# Sensor_tile.net
KiCad netlist of a schematic drawn in EAGLE
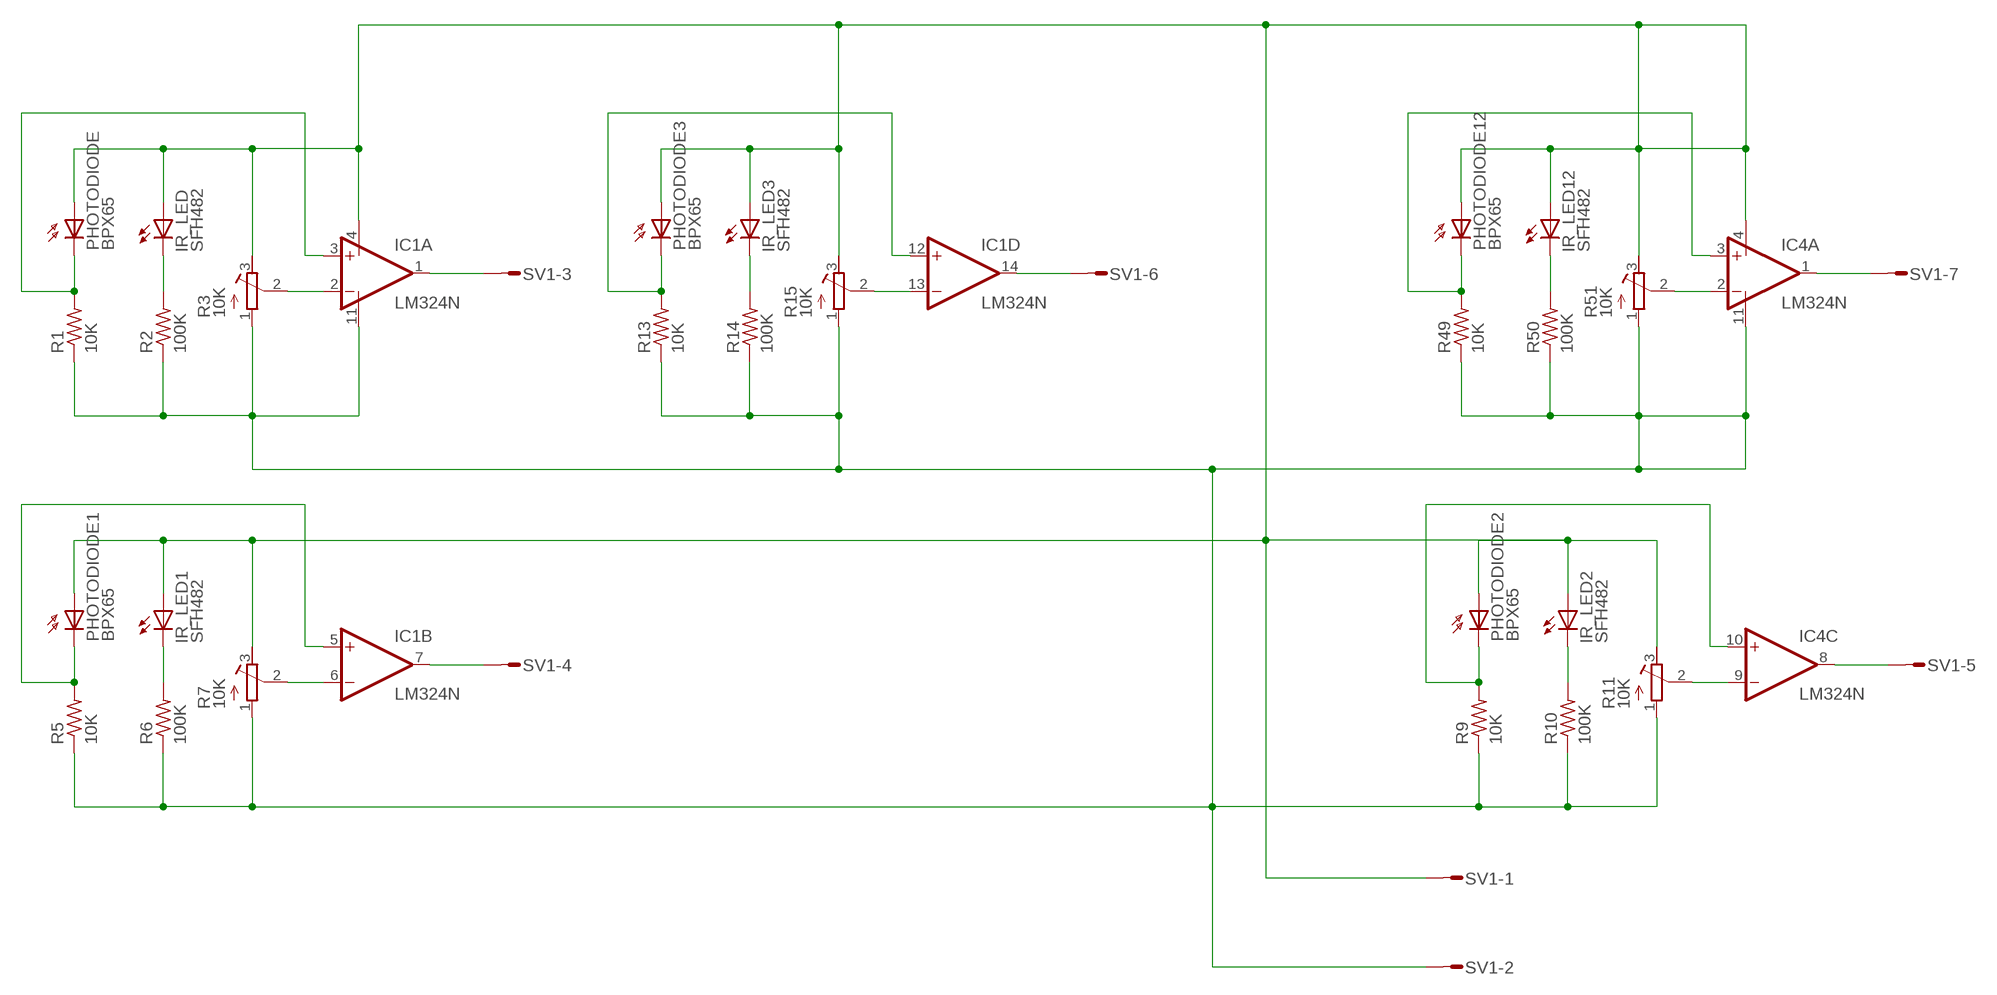
[diagram p0: schematic, sheet 1]

(export (version "E")
  (design (tool "Eeschema 10.0.6"))
  (components
    (comp (ref "IC1")
      (value "LM324N")
      (footprint "eagle-import:DIL14")
      (libsource (lib "eagle-import") (part "LM324N"))
    )
    (comp (ref "IC4")
      (value "LM324N")
      (footprint "eagle-import:DIL14")
      (libsource (lib "eagle-import") (part "LM324N"))
    )
    (comp (ref "IR_LED")
      (value "SFH482")
      (footprint "eagle-import:SFH482")
      (libsource (lib "eagle-import") (part "SFH482"))
    )
    (comp (ref "IR_LED1")
      (value "SFH482")
      (footprint "eagle-import:SFH482")
      (libsource (lib "eagle-import") (part "SFH482"))
    )
    (comp (ref "IR_LED2")
      (value "SFH482")
      (footprint "eagle-import:SFH482")
      (libsource (lib "eagle-import") (part "SFH482"))
    )
    (comp (ref "IR_LED3")
      (value "SFH482")
      (footprint "eagle-import:SFH482")
      (libsource (lib "eagle-import") (part "SFH482"))
    )
    (comp (ref "IR_LED12")
      (value "SFH482")
      (footprint "eagle-import:SFH482")
      (libsource (lib "eagle-import") (part "SFH482"))
    )
    (comp (ref "PHOTODIODE")
      (value "BPX65")
      (footprint "eagle-import:BPX65")
      (fields (field (name "MPN") "BPX65."))
      (libsource (lib "eagle-import") (part "BPX65"))
    )
    (comp (ref "PHOTODIODE1")
      (value "BPX65")
      (footprint "eagle-import:BPX65")
      (fields (field (name "MPN") "BPX65."))
      (libsource (lib "eagle-import") (part "BPX65"))
    )
    (comp (ref "PHOTODIODE2")
      (value "BPX65")
      (footprint "eagle-import:BPX65")
      (fields (field (name "MPN") "BPX65."))
      (libsource (lib "eagle-import") (part "BPX65"))
    )
    (comp (ref "PHOTODIODE3")
      (value "BPX65")
      (footprint "eagle-import:BPX65")
      (fields (field (name "MPN") "BPX65."))
      (libsource (lib "eagle-import") (part "BPX65"))
    )
    (comp (ref "PHOTODIODE12")
      (value "BPX65")
      (footprint "eagle-import:BPX65")
      (fields (field (name "MPN") "BPX65."))
      (libsource (lib "eagle-import") (part "BPX65"))
    )
    (comp (ref "R1")
      (value "10K")
      (footprint "eagle-import:0204_7")
      (libsource (lib "eagle-import") (part "R-US_0204/7"))
    )
    (comp (ref "R2")
      (value "100K")
      (footprint "eagle-import:0204_7")
      (libsource (lib "eagle-import") (part "R-US_0204/7"))
    )
    (comp (ref "R3")
      (value "10K")
      (footprint "eagle-import:RTRIM4G_J")
      (libsource (lib "eagle-import") (part "R-TRIMM4G/J"))
    )
    (comp (ref "R5")
      (value "10K")
      (footprint "eagle-import:0204_7")
      (libsource (lib "eagle-import") (part "R-US_0204/7"))
    )
    (comp (ref "R6")
      (value "100K")
      (footprint "eagle-import:0204_7")
      (libsource (lib "eagle-import") (part "R-US_0204/7"))
    )
    (comp (ref "R7")
      (value "10K")
      (footprint "eagle-import:RTRIM4G_J")
      (libsource (lib "eagle-import") (part "R-TRIMM4G/J"))
    )
    (comp (ref "R9")
      (value "10K")
      (footprint "eagle-import:0204_7")
      (libsource (lib "eagle-import") (part "R-US_0204/7"))
    )
    (comp (ref "R10")
      (value "100K")
      (footprint "eagle-import:0204_7")
      (libsource (lib "eagle-import") (part "R-US_0204/7"))
    )
    (comp (ref "R11")
      (value "10K")
      (footprint "eagle-import:RTRIM4G_J")
      (libsource (lib "eagle-import") (part "R-TRIMM4G/J"))
    )
    (comp (ref "R13")
      (value "10K")
      (footprint "eagle-import:0204_7")
      (libsource (lib "eagle-import") (part "R-US_0204/7"))
    )
    (comp (ref "R14")
      (value "100K")
      (footprint "eagle-import:0204_7")
      (libsource (lib "eagle-import") (part "R-US_0204/7"))
    )
    (comp (ref "R15")
      (value "10K")
      (footprint "eagle-import:RTRIM4G_J")
      (libsource (lib "eagle-import") (part "R-TRIMM4G/J"))
    )
    (comp (ref "R49")
      (value "10K")
      (footprint "eagle-import:0204_7")
      (libsource (lib "eagle-import") (part "R-US_0204/7"))
    )
    (comp (ref "R50")
      (value "100K")
      (footprint "eagle-import:0204_7")
      (libsource (lib "eagle-import") (part "R-US_0204/7"))
    )
    (comp (ref "R51")
      (value "10K")
      (footprint "eagle-import:RTRIM4G_J")
      (libsource (lib "eagle-import") (part "R-TRIMM4G/J"))
    )
    (comp (ref "SV1")
      (value "L07P")
      (footprint "eagle-import:L07P")
      (libsource (lib "eagle-import") (part "L07P"))
    )
  )
  (nets
    (net (code "1") (name "Net-(IC1A-+IN)") (class "Default")
      (node (ref "IC1") (pin "3") (pinfunction "+IN_3") (pintype "input"))
      (node (ref "PHOTODIODE") (pin "K") (pinfunction "C_K") (pintype "passive"))
      (node (ref "R1") (pin "2") (pinfunction "2_2") (pintype "passive"))
    )
    (net (code "2") (name "Net-(IC1A--IN)") (class "Default")
      (node (ref "IC1") (pin "2") (pinfunction "-IN_2") (pintype "input"))
      (node (ref "R3") (pin "2") (pinfunction "S_2") (pintype "passive"))
    )
    (net (code "3") (name "Net-(IC1A-OUT)") (class "Default")
      (node (ref "IC1") (pin "1") (pinfunction "OUT_1") (pintype "output"))
      (node (ref "SV1") (pin "3") (pinfunction "S_3") (pintype "passive"))
    )
    (net (code "4") (name "Net-(IC1B-+IN)") (class "Default")
      (node (ref "IC1") (pin "5") (pinfunction "+IN_5") (pintype "input"))
      (node (ref "PHOTODIODE1") (pin "K") (pinfunction "C_K") (pintype "passive"))
      (node (ref "R5") (pin "2") (pinfunction "2_2") (pintype "passive"))
    )
    (net (code "5") (name "Net-(IC1B--IN)") (class "Default")
      (node (ref "IC1") (pin "6") (pinfunction "-IN_6") (pintype "input"))
      (node (ref "R7") (pin "2") (pinfunction "S_2") (pintype "passive"))
    )
    (net (code "6") (name "Net-(IC1B-OUT)") (class "Default")
      (node (ref "IC1") (pin "7") (pinfunction "OUT_7") (pintype "output"))
      (node (ref "SV1") (pin "4") (pinfunction "S_4") (pintype "passive"))
    )
    (net (code "7") (name "Net-(IC1D-+IN)") (class "Default")
      (node (ref "IC1") (pin "12") (pinfunction "+IN_12") (pintype "input"))
      (node (ref "PHOTODIODE3") (pin "K") (pinfunction "C_K") (pintype "passive"))
      (node (ref "R13") (pin "2") (pinfunction "2_2") (pintype "passive"))
    )
    (net (code "8") (name "Net-(IC1D--IN)") (class "Default")
      (node (ref "IC1") (pin "13") (pinfunction "-IN_13") (pintype "input"))
      (node (ref "R15") (pin "2") (pinfunction "S_2") (pintype "passive"))
    )
    (net (code "9") (name "Net-(IC1D-OUT)") (class "Default")
      (node (ref "IC1") (pin "14") (pinfunction "OUT_14") (pintype "output"))
      (node (ref "SV1") (pin "6") (pinfunction "S_6") (pintype "passive"))
    )
    (net (code "10") (name "Net-(IC1E-V+)") (class "Default")
      (node (ref "IC1") (pin "4") (pinfunction "V+_4") (pintype "power_in"))
      (node (ref "IC4") (pin "4") (pinfunction "V+_4") (pintype "power_in"))
      (node (ref "IR_LED") (pin "A") (pinfunction "A_A") (pintype "passive"))
      (node (ref "IR_LED1") (pin "A") (pinfunction "A_A") (pintype "passive"))
      (node (ref "IR_LED12") (pin "A") (pinfunction "A_A") (pintype "passive"))
      (node (ref "IR_LED2") (pin "A") (pinfunction "A_A") (pintype "passive"))
      (node (ref "IR_LED3") (pin "A") (pinfunction "A_A") (pintype "passive"))
      (node (ref "PHOTODIODE") (pin "A") (pinfunction "A_A") (pintype "passive"))
      (node (ref "PHOTODIODE1") (pin "A") (pinfunction "A_A") (pintype "passive"))
      (node (ref "PHOTODIODE12") (pin "A") (pinfunction "A_A") (pintype "passive"))
      (node (ref "PHOTODIODE2") (pin "A") (pinfunction "A_A") (pintype "passive"))
      (node (ref "PHOTODIODE3") (pin "A") (pinfunction "A_A") (pintype "passive"))
      (node (ref "R11") (pin "3") (pinfunction "E_3") (pintype "passive"))
      (node (ref "R15") (pin "3") (pinfunction "E_3") (pintype "passive"))
      (node (ref "R3") (pin "3") (pinfunction "E_3") (pintype "passive"))
      (node (ref "R51") (pin "3") (pinfunction "E_3") (pintype "passive"))
      (node (ref "R7") (pin "3") (pinfunction "E_3") (pintype "passive"))
      (node (ref "SV1") (pin "1") (pinfunction "S_1") (pintype "passive"))
    )
    (net (code "11") (name "Net-(IC1E-V-)") (class "Default")
      (node (ref "IC1") (pin "11") (pinfunction "V-_11") (pintype "power_in"))
      (node (ref "IC4") (pin "11") (pinfunction "V-_11") (pintype "power_in"))
      (node (ref "R1") (pin "1") (pinfunction "1_1") (pintype "passive"))
      (node (ref "R10") (pin "1") (pinfunction "1_1") (pintype "passive"))
      (node (ref "R11") (pin "1") (pinfunction "A_1") (pintype "passive"))
      (node (ref "R13") (pin "1") (pinfunction "1_1") (pintype "passive"))
      (node (ref "R14") (pin "1") (pinfunction "1_1") (pintype "passive"))
      (node (ref "R15") (pin "1") (pinfunction "A_1") (pintype "passive"))
      (node (ref "R2") (pin "1") (pinfunction "1_1") (pintype "passive"))
      (node (ref "R3") (pin "1") (pinfunction "A_1") (pintype "passive"))
      (node (ref "R49") (pin "1") (pinfunction "1_1") (pintype "passive"))
      (node (ref "R5") (pin "1") (pinfunction "1_1") (pintype "passive"))
      (node (ref "R50") (pin "1") (pinfunction "1_1") (pintype "passive"))
      (node (ref "R51") (pin "1") (pinfunction "A_1") (pintype "passive"))
      (node (ref "R6") (pin "1") (pinfunction "1_1") (pintype "passive"))
      (node (ref "R7") (pin "1") (pinfunction "A_1") (pintype "passive"))
      (node (ref "R9") (pin "1") (pinfunction "1_1") (pintype "passive"))
      (node (ref "SV1") (pin "2") (pinfunction "S_2") (pintype "passive"))
    )
    (net (code "12") (name "Net-(IC4A-+IN)") (class "Default")
      (node (ref "IC4") (pin "3") (pinfunction "+IN_3") (pintype "input"))
      (node (ref "PHOTODIODE12") (pin "K") (pinfunction "C_K") (pintype "passive"))
      (node (ref "R49") (pin "2") (pinfunction "2_2") (pintype "passive"))
    )
    (net (code "13") (name "Net-(IC4A--IN)") (class "Default")
      (node (ref "IC4") (pin "2") (pinfunction "-IN_2") (pintype "input"))
      (node (ref "R51") (pin "2") (pinfunction "S_2") (pintype "passive"))
    )
    (net (code "14") (name "Net-(IC4A-OUT)") (class "Default")
      (node (ref "IC4") (pin "1") (pinfunction "OUT_1") (pintype "output"))
      (node (ref "SV1") (pin "7") (pinfunction "S_7") (pintype "passive"))
    )
    (net (code "15") (name "Net-(IC4C-+IN)") (class "Default")
      (node (ref "IC4") (pin "10") (pinfunction "+IN_10") (pintype "input"))
      (node (ref "PHOTODIODE2") (pin "K") (pinfunction "C_K") (pintype "passive"))
      (node (ref "R9") (pin "2") (pinfunction "2_2") (pintype "passive"))
    )
    (net (code "16") (name "Net-(IC4C--IN)") (class "Default")
      (node (ref "IC4") (pin "9") (pinfunction "-IN_9") (pintype "input"))
      (node (ref "R11") (pin "2") (pinfunction "S_2") (pintype "passive"))
    )
    (net (code "17") (name "Net-(IC4C-OUT)") (class "Default")
      (node (ref "IC4") (pin "8") (pinfunction "OUT_8") (pintype "output"))
      (node (ref "SV1") (pin "5") (pinfunction "S_5") (pintype "passive"))
    )
    (net (code "18") (name "Net-(IR_LED-C)") (class "Default")
      (node (ref "IR_LED") (pin "K") (pinfunction "C_K") (pintype "passive"))
      (node (ref "R2") (pin "2") (pinfunction "2_2") (pintype "passive"))
    )
    (net (code "19") (name "Net-(IR_LED1-C)") (class "Default")
      (node (ref "IR_LED1") (pin "K") (pinfunction "C_K") (pintype "passive"))
      (node (ref "R6") (pin "2") (pinfunction "2_2") (pintype "passive"))
    )
    (net (code "20") (name "Net-(IR_LED2-C)") (class "Default")
      (node (ref "IR_LED2") (pin "K") (pinfunction "C_K") (pintype "passive"))
      (node (ref "R10") (pin "2") (pinfunction "2_2") (pintype "passive"))
    )
    (net (code "21") (name "Net-(IR_LED3-C)") (class "Default")
      (node (ref "IR_LED3") (pin "K") (pinfunction "C_K") (pintype "passive"))
      (node (ref "R14") (pin "2") (pinfunction "2_2") (pintype "passive"))
    )
    (net (code "22") (name "Net-(IR_LED12-C)") (class "Default")
      (node (ref "IR_LED12") (pin "K") (pinfunction "C_K") (pintype "passive"))
      (node (ref "R50") (pin "2") (pinfunction "2_2") (pintype "passive"))
    )
  )
)
